# hub.net
KiCad netlist of a schematic drawn in Altium Designer
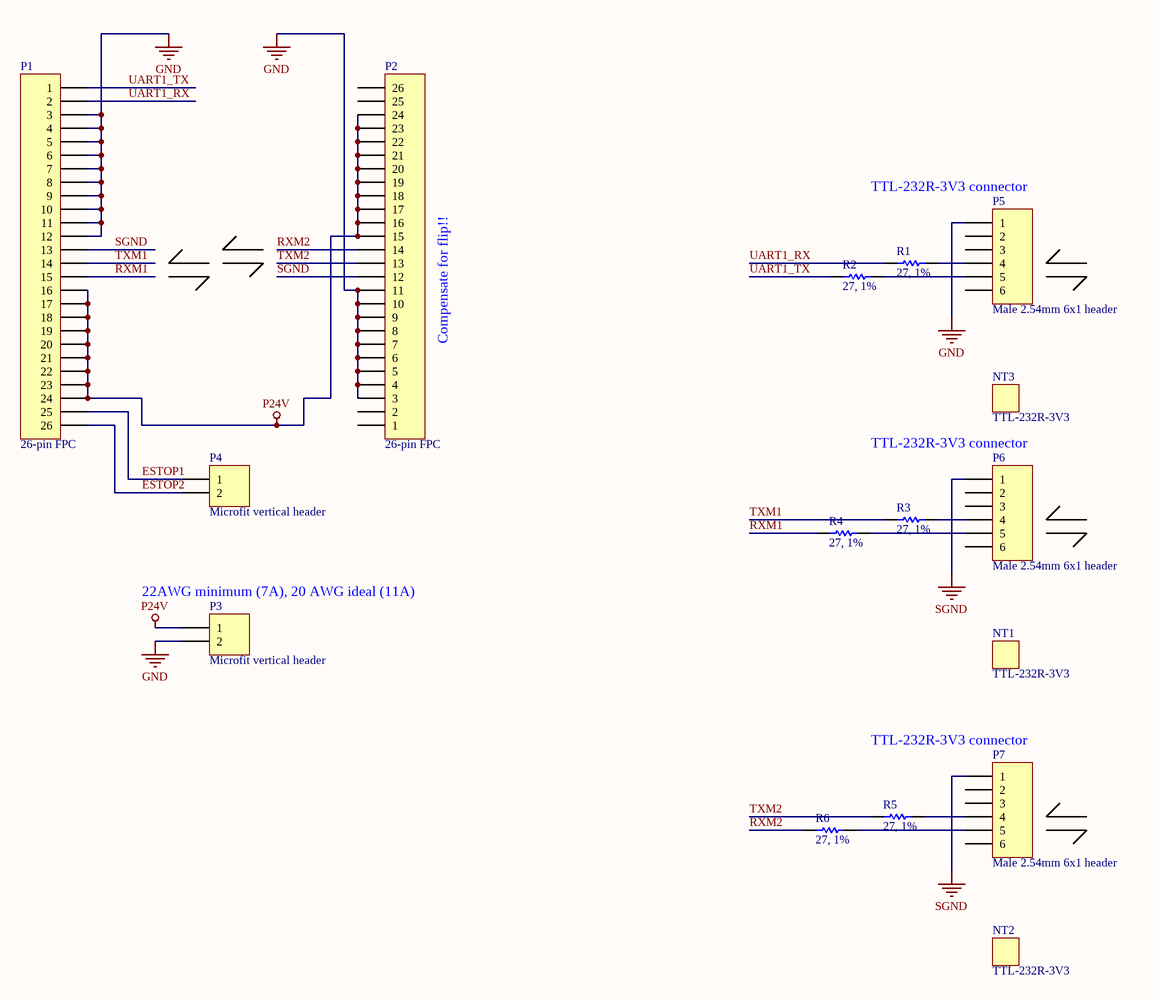
[diagram p0: hub.SchDoc]

(export (version "E")
  (design (tool "Eeschema 10.0.6"))
  (components
    (comp (ref "NT1")
      (value "TTL-232R-3V3")
      (description "Placeholder for non-board BOM items")
      (libsource (lib "commonsch") (part "NOTE"))
    )
    (comp (ref "NT2")
      (value "TTL-232R-3V3")
      (description "Placeholder for non-board BOM items")
      (libsource (lib "commonsch") (part "NOTE"))
    )
    (comp (ref "NT3")
      (value "TTL-232R-3V3")
      (description "Placeholder for non-board BOM items")
      (libsource (lib "commonsch") (part "NOTE"))
    )
    (comp (ref "P1")
      (value "26-pin FPC")
      (footprint "HRS_FH34SRJ-26S-0.5SH(50)")
      (description "26 Pin FPC header")
      (fields (field (name "MPN") "FH34SRJ-26S-0.5SH(99)"))
      (libsource (lib "") (part "FPC-26_1"))
    )
    (comp (ref "P2")
      (value "26-pin FPC")
      (footprint "HRS_FH34SRJ-26S-0.5SH(50)")
      (description "26 Pin FPC header")
      (fields (field (name "MPN") "FH34SRJ-26S-0.5SH(99)"))
      (libsource (lib "commonsch-new") (part "FPC-26"))
    )
    (comp (ref "P3")
      (value "Microfit vertical header")
      (footprint "MOLEX_0436500217")
      (description "Header, 2-Pin")
      (fields (field (name "MPN") "0436500217") (field (name "PUBLISHER") "Altium Limited"))
      (libsource (lib "Miscellaneous Connectors") (part "Header 2"))
    )
    (comp (ref "P4")
      (value "Microfit vertical header")
      (footprint "MOLEX_0436500217")
      (description "Header, 2-Pin")
      (fields (field (name "MPN") "0436500217") (field (name "PUBLISHER") "Altium Limited"))
      (libsource (lib "Miscellaneous Connectors") (part "Header 2"))
    )
    (comp (ref "P5")
      (value "Male 2.54mm 6x1 header")
      (footprint "HDR1X6")
      (description "Header, 6-Pin")
      (fields (field (name "MPN") "PH1-06-UA / ANY") (field (name "PUBLISHER") "Altium Limited"))
      (libsource (lib "Miscellaneous Connectors") (part "Header 6"))
    )
    (comp (ref "P6")
      (value "Male 2.54mm 6x1 header")
      (footprint "HDR1X6")
      (description "Header, 6-Pin")
      (fields (field (name "MPN") "PH1-06-UA / ANY") (field (name "PUBLISHER") "Altium Limited"))
      (libsource (lib "Miscellaneous Connectors") (part "Header 6"))
    )
    (comp (ref "P7")
      (value "Male 2.54mm 6x1 header")
      (footprint "HDR1X6")
      (description "Header, 6-Pin")
      (fields (field (name "MPN") "PH1-06-UA / ANY") (field (name "PUBLISHER") "Altium Limited"))
      (libsource (lib "Miscellaneous Connectors") (part "Header 6"))
    )
    (comp (ref "R1")
      (value "27, 1%")
      (footprint "B_RES0603")
      (description "Resistor")
      (fields (field (name "MPN") "ANY"))
      (libsource (lib "Miscellaneous Devices") (part "Res1"))
    )
    (comp (ref "R2")
      (value "27, 1%")
      (footprint "B_RES0603")
      (description "Resistor")
      (fields (field (name "MPN") "ANY"))
      (libsource (lib "Miscellaneous Devices") (part "Res1"))
    )
    (comp (ref "R3")
      (value "27, 1%")
      (footprint "B_RES0603")
      (description "Resistor")
      (fields (field (name "MPN") "ANY"))
      (libsource (lib "Miscellaneous Devices") (part "Res1"))
    )
    (comp (ref "R4")
      (value "27, 1%")
      (footprint "B_RES0603")
      (description "Resistor")
      (fields (field (name "MPN") "ANY"))
      (libsource (lib "Miscellaneous Devices") (part "Res1"))
    )
    (comp (ref "R5")
      (value "27, 1%")
      (footprint "B_RES0603")
      (description "Resistor")
      (fields (field (name "MPN") "ANY"))
      (libsource (lib "Miscellaneous Devices") (part "Res1"))
    )
    (comp (ref "R6")
      (value "27, 1%")
      (footprint "B_RES0603")
      (description "Resistor")
      (fields (field (name "MPN") "ANY"))
      (libsource (lib "Miscellaneous Devices") (part "Res1"))
    )
  )
  (nets
    (net (code "1") (name "/ESTOP1") (class "Default")
      (node (ref "P1") (pin "25") (pinfunction "25_25") (pintype "passive"))
      (node (ref "P4") (pin "1") (pinfunction "1_1") (pintype "passive"))
    )
    (net (code "2") (name "/ESTOP2") (class "Default")
      (node (ref "P1") (pin "26") (pinfunction "26_26") (pintype "passive"))
      (node (ref "P4") (pin "2") (pinfunction "2_2") (pintype "passive"))
    )
    (net (code "3") (name "/RXM1") (class "Default")
      (node (ref "P1") (pin "15") (pinfunction "15_15") (pintype "passive"))
      (node (ref "R4") (pin "1") (pinfunction "1_1") (pintype "passive"))
    )
    (net (code "4") (name "/RXM2") (class "Default")
      (node (ref "P2") (pin "14") (pinfunction "14_14") (pintype "passive"))
      (node (ref "R6") (pin "1") (pinfunction "1_1") (pintype "passive"))
    )
    (net (code "5") (name "/TXM1") (class "Default")
      (node (ref "P1") (pin "14") (pinfunction "14_14") (pintype "passive"))
      (node (ref "R3") (pin "1") (pinfunction "1_1") (pintype "passive"))
    )
    (net (code "6") (name "/TXM2") (class "Default")
      (node (ref "P2") (pin "13") (pinfunction "13_13") (pintype "passive"))
      (node (ref "R5") (pin "1") (pinfunction "1_1") (pintype "passive"))
    )
    (net (code "7") (name "/UART1_RX") (class "Default")
      (node (ref "P1") (pin "2") (pinfunction "2_2") (pintype "passive"))
      (node (ref "R1") (pin "1") (pinfunction "1_1") (pintype "passive"))
    )
    (net (code "8") (name "/UART1_TX") (class "Default")
      (node (ref "P1") (pin "1") (pinfunction "1_1") (pintype "passive"))
      (node (ref "R2") (pin "1") (pinfunction "1_1") (pintype "passive"))
    )
    (net (code "9") (name "GND") (class "Default")
      (node (ref "P1") (pin "10") (pinfunction "10_10") (pintype "passive"))
      (node (ref "P1") (pin "11") (pinfunction "11_11") (pintype "passive"))
      (node (ref "P1") (pin "12") (pinfunction "12_12") (pintype "passive"))
      (node (ref "P1") (pin "3") (pinfunction "3_3") (pintype "passive"))
      (node (ref "P1") (pin "4") (pinfunction "4_4") (pintype "passive"))
      (node (ref "P1") (pin "5") (pinfunction "5_5") (pintype "passive"))
      (node (ref "P1") (pin "6") (pinfunction "6_6") (pintype "passive"))
      (node (ref "P1") (pin "7") (pinfunction "7_7") (pintype "passive"))
      (node (ref "P1") (pin "8") (pinfunction "8_8") (pintype "passive"))
      (node (ref "P1") (pin "9") (pinfunction "9_9") (pintype "passive"))
      (node (ref "P2") (pin "10") (pinfunction "10_10") (pintype "passive"))
      (node (ref "P2") (pin "11") (pinfunction "11_11") (pintype "passive"))
      (node (ref "P2") (pin "3") (pinfunction "3_3") (pintype "passive"))
      (node (ref "P2") (pin "4") (pinfunction "4_4") (pintype "passive"))
      (node (ref "P2") (pin "5") (pinfunction "5_5") (pintype "passive"))
      (node (ref "P2") (pin "6") (pinfunction "6_6") (pintype "passive"))
      (node (ref "P2") (pin "7") (pinfunction "7_7") (pintype "passive"))
      (node (ref "P2") (pin "8") (pinfunction "8_8") (pintype "passive"))
      (node (ref "P2") (pin "9") (pinfunction "9_9") (pintype "passive"))
      (node (ref "P3") (pin "2") (pinfunction "2_2") (pintype "passive"))
      (node (ref "P5") (pin "1") (pinfunction "1_1") (pintype "passive"))
    )
    (net (code "10") (name "Net-(P5-Pad4)") (class "Default")
      (node (ref "P5") (pin "4") (pinfunction "4_4") (pintype "passive"))
      (node (ref "R1") (pin "2") (pinfunction "2_2") (pintype "passive"))
    )
    (net (code "11") (name "Net-(P5-Pad5)") (class "Default")
      (node (ref "P5") (pin "5") (pinfunction "5_5") (pintype "passive"))
      (node (ref "R2") (pin "2") (pinfunction "2_2") (pintype "passive"))
    )
    (net (code "12") (name "Net-(P6-Pad4)") (class "Default")
      (node (ref "P6") (pin "4") (pinfunction "4_4") (pintype "passive"))
      (node (ref "R3") (pin "2") (pinfunction "2_2") (pintype "passive"))
    )
    (net (code "13") (name "Net-(P6-Pad5)") (class "Default")
      (node (ref "P6") (pin "5") (pinfunction "5_5") (pintype "passive"))
      (node (ref "R4") (pin "2") (pinfunction "2_2") (pintype "passive"))
    )
    (net (code "14") (name "Net-(P7-Pad4)") (class "Default")
      (node (ref "P7") (pin "4") (pinfunction "4_4") (pintype "passive"))
      (node (ref "R5") (pin "2") (pinfunction "2_2") (pintype "passive"))
    )
    (net (code "15") (name "Net-(P7-Pad5)") (class "Default")
      (node (ref "P7") (pin "5") (pinfunction "5_5") (pintype "passive"))
      (node (ref "R6") (pin "2") (pinfunction "2_2") (pintype "passive"))
    )
    (net (code "16") (name "P24V") (class "Default")
      (node (ref "P1") (pin "16") (pinfunction "16_16") (pintype "passive"))
      (node (ref "P1") (pin "17") (pinfunction "17_17") (pintype "passive"))
      (node (ref "P1") (pin "18") (pinfunction "18_18") (pintype "passive"))
      (node (ref "P1") (pin "19") (pinfunction "19_19") (pintype "passive"))
      (node (ref "P1") (pin "20") (pinfunction "20_20") (pintype "passive"))
      (node (ref "P1") (pin "21") (pinfunction "21_21") (pintype "passive"))
      (node (ref "P1") (pin "22") (pinfunction "22_22") (pintype "passive"))
      (node (ref "P1") (pin "23") (pinfunction "23_23") (pintype "passive"))
      (node (ref "P1") (pin "24") (pinfunction "24_24") (pintype "passive"))
      (node (ref "P2") (pin "15") (pinfunction "15_15") (pintype "passive"))
      (node (ref "P2") (pin "16") (pinfunction "16_16") (pintype "passive"))
      (node (ref "P2") (pin "17") (pinfunction "17_17") (pintype "passive"))
      (node (ref "P2") (pin "18") (pinfunction "18_18") (pintype "passive"))
      (node (ref "P2") (pin "19") (pinfunction "19_19") (pintype "passive"))
      (node (ref "P2") (pin "20") (pinfunction "20_20") (pintype "passive"))
      (node (ref "P2") (pin "21") (pinfunction "21_21") (pintype "passive"))
      (node (ref "P2") (pin "22") (pinfunction "22_22") (pintype "passive"))
      (node (ref "P2") (pin "23") (pinfunction "23_23") (pintype "passive"))
      (node (ref "P2") (pin "24") (pinfunction "24_24") (pintype "passive"))
      (node (ref "P3") (pin "1") (pinfunction "1_1") (pintype "passive"))
    )
    (net (code "17") (name "SGND") (class "Default")
      (node (ref "P1") (pin "13") (pinfunction "13_13") (pintype "passive"))
      (node (ref "P2") (pin "12") (pinfunction "12_12") (pintype "passive"))
      (node (ref "P6") (pin "1") (pinfunction "1_1") (pintype "passive"))
      (node (ref "P7") (pin "1") (pinfunction "1_1") (pintype "passive"))
    )
    (net (code "18") (name "unconnected-(P2-Pad1)") (class "Default")
      (node (ref "P2") (pin "1") (pinfunction "1_1") (pintype "passive"))
    )
    (net (code "19") (name "unconnected-(P2-Pad2)") (class "Default")
      (node (ref "P2") (pin "2") (pinfunction "2_2") (pintype "passive"))
    )
    (net (code "20") (name "unconnected-(P2-Pad25)") (class "Default")
      (node (ref "P2") (pin "25") (pinfunction "25_25") (pintype "passive"))
    )
    (net (code "21") (name "unconnected-(P2-Pad26)") (class "Default")
      (node (ref "P2") (pin "26") (pinfunction "26_26") (pintype "passive"))
    )
    (net (code "22") (name "unconnected-(P5-Pad2)") (class "Default")
      (node (ref "P5") (pin "2") (pinfunction "2_2") (pintype "passive"))
    )
    (net (code "23") (name "unconnected-(P5-Pad3)") (class "Default")
      (node (ref "P5") (pin "3") (pinfunction "3_3") (pintype "passive"))
    )
    (net (code "24") (name "unconnected-(P5-Pad6)") (class "Default")
      (node (ref "P5") (pin "6") (pinfunction "6_6") (pintype "passive"))
    )
    (net (code "25") (name "unconnected-(P6-Pad2)") (class "Default")
      (node (ref "P6") (pin "2") (pinfunction "2_2") (pintype "passive"))
    )
    (net (code "26") (name "unconnected-(P6-Pad3)") (class "Default")
      (node (ref "P6") (pin "3") (pinfunction "3_3") (pintype "passive"))
    )
    (net (code "27") (name "unconnected-(P6-Pad6)") (class "Default")
      (node (ref "P6") (pin "6") (pinfunction "6_6") (pintype "passive"))
    )
    (net (code "28") (name "unconnected-(P7-Pad2)") (class "Default")
      (node (ref "P7") (pin "2") (pinfunction "2_2") (pintype "passive"))
    )
    (net (code "29") (name "unconnected-(P7-Pad3)") (class "Default")
      (node (ref "P7") (pin "3") (pinfunction "3_3") (pintype "passive"))
    )
    (net (code "30") (name "unconnected-(P7-Pad6)") (class "Default")
      (node (ref "P7") (pin "6") (pinfunction "6_6") (pintype "passive"))
    )
  )
)
